# 02_-_POWER.net
KiCad netlist of a schematic drawn in Altium Designer
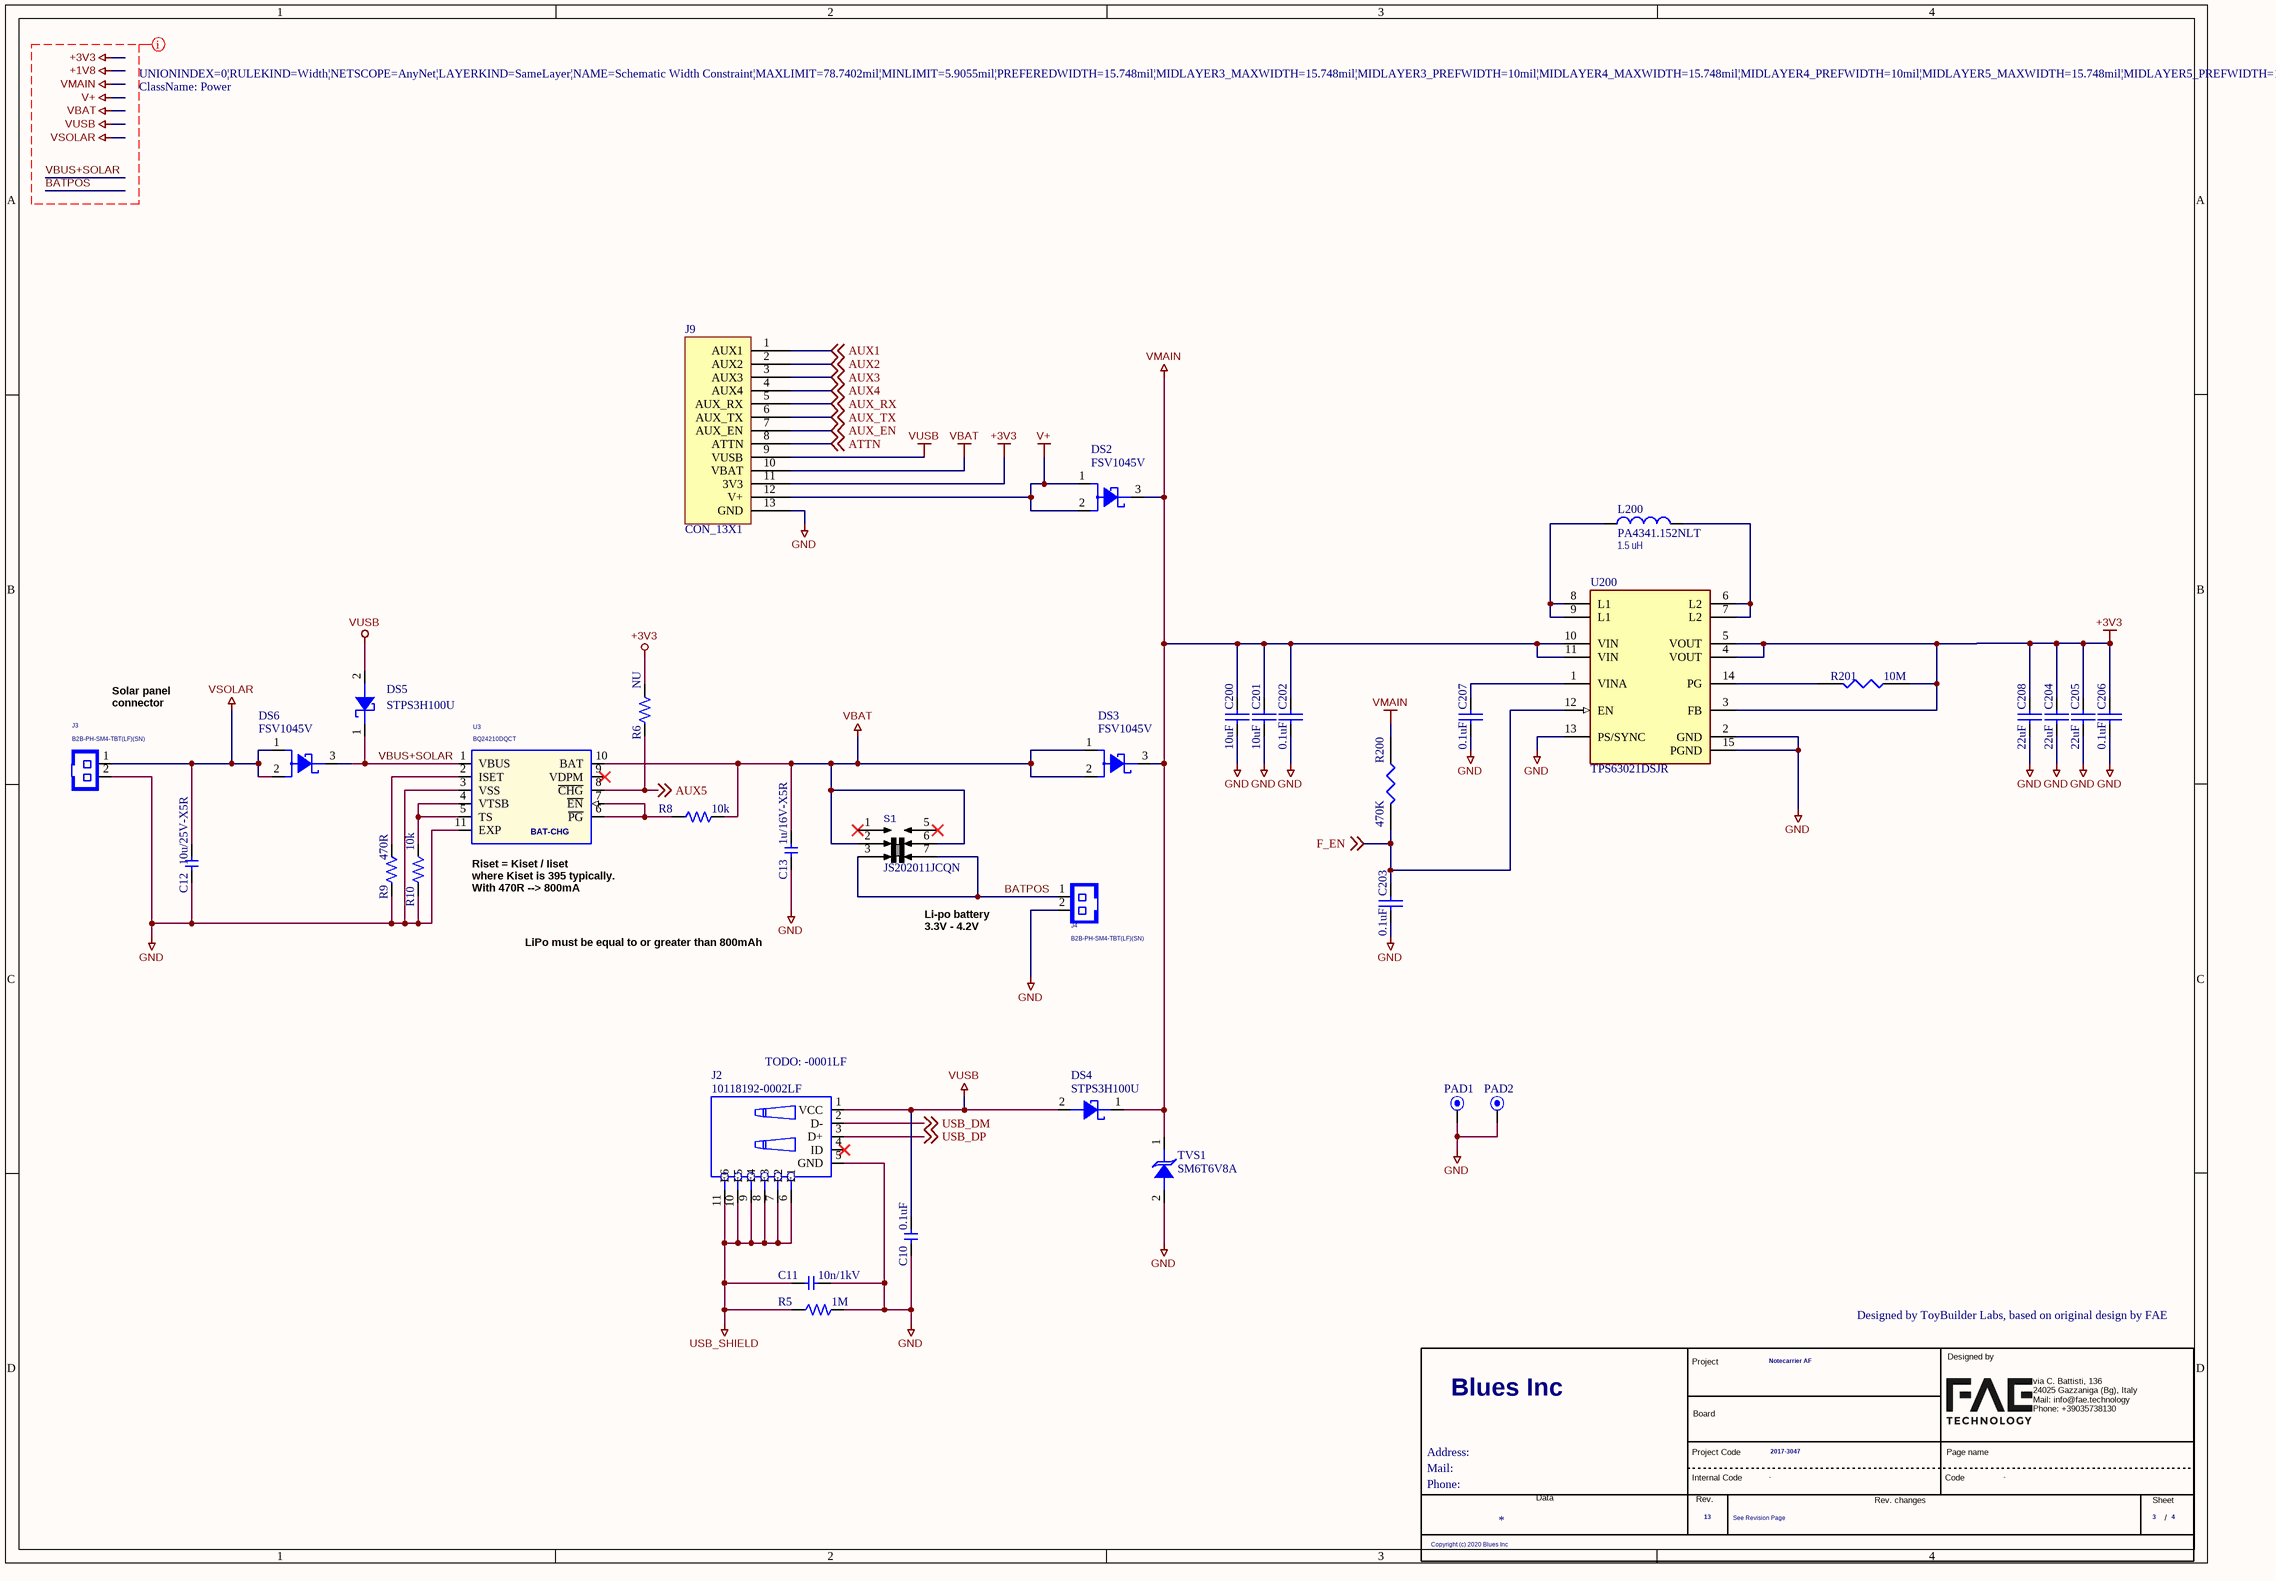
[diagram p0: 02 - POWER.SchDoc]

(export (version "E")
  (design (tool "Eeschema 10.0.6"))
  (components
    (comp (ref "*")
      (value "MyBlues")
      (fields
        (field (name "ADDRESS") "Address:")
        (field (name "COPYRIGHT") "Copyright (c) 2020 Blues Inc")
        (field (name "CUSTOMER CODE") "-")
        (field (name "CUSTOMERNAME") "Blues Inc")
        (field (name "DATABASE") "-")
        (field (name "DOCUMENTOREV") "See Revision Page")
        (field (name "MAIL") "Mail:")
        (field (name "NOME PROGETTO") "Notecarrier AF")
        (field (name "PAGE COUNT") "4")
        (field (name "PAGE NUMBER") "3")
        (field (name "PHONE") "Phone:")
        (field (name "PROJECT CODE") "2017-3047")
        (field (name "REVISION") "13")
      )
      (libsource (lib "*") (part "MyBlues"))
    )
    (comp (ref "C10")
      (value "0.1uF")
      (footprint "CS-C-0402")
      (description "CHIP CAP.CER. 100nF 16V 10% X7R 0402")
      (fields (field (name "MFR") "Yageo"))
      (libsource (lib "*") (part "CS-C-0402-100n/16V"))
    )
    (comp (ref "C11")
      (value "10n/1kV")
      (footprint "CS-C-1206")
      (description "CHIP CAP.CER. 10nF 1000V 10% X7R 1206")
      (libsource (lib "*") (part "CS-C-1206-10n/1kV"))
    )
    (comp (ref "C12")
      (value "10u/25V-X5R")
      (footprint "CS-C-1206")
      (description "CHIP CAP.CER. 10uF 25V X5R 10% 1206")
      (libsource (lib "*") (part "CS-C-1206-10u/25V-X5R"))
    )
    (comp (ref "C13")
      (value "1u/16V-X5R")
      (footprint "CS-C-0402")
      (description "CHIP CAP.CER. 1uF 16V 10% X5R 0402")
      (libsource (lib "*") (part "CS-C-0402-1u/16-X5R"))
    )
    (comp (ref "C200")
      (value "10uF")
      (footprint "0805_C")
      (description "CHIP CAP.CER. 10uF 16V 10% X7R 0805")
      (fields (field (name "MFR") "TDK"))
      (libsource (lib "Cap_SCH") (part "CAP"))
    )
    (comp (ref "C201")
      (value "10uF")
      (footprint "0805_C")
      (description "CHIP CAP.CER. 10uF 16V 10% X7R 0805")
      (fields (field (name "MFR") "TDK"))
      (libsource (lib "Cap_SCH") (part "CAP"))
    )
    (comp (ref "C202")
      (value "0.1uF")
      (footprint "CS-C-0402")
      (description "CHIP CAP.CER. 100nF 16V 10% X7R 0402")
      (fields (field (name "MFR") "Yageo"))
      (libsource (lib "Cap_SCH") (part "CAP"))
    )
    (comp (ref "C203")
      (value "0.1uF")
      (footprint "CS-C-0402")
      (description "CHIP CAP.CER. 100nF 16V 10% X7R 0402")
      (fields (field (name "MFR") "Yageo"))
      (libsource (lib "Cap_SCH") (part "CAP"))
    )
    (comp (ref "C204")
      (value "22uF")
      (footprint "0805_C")
      (description "CHIP CAP.CER. 22uF 16V 10% X7R 0805")
      (fields (field (name "MFR") "TDK"))
      (libsource (lib "Cap_SCH") (part "CAP"))
    )
    (comp (ref "C205")
      (value "22uF")
      (footprint "0805_C")
      (description "CHIP CAP.CER. 22uF 16V 10% X7R 0805")
      (fields (field (name "MFR") "TDK"))
      (libsource (lib "Cap_SCH") (part "CAP"))
    )
    (comp (ref "C206")
      (value "0.1uF")
      (footprint "CS-C-0402")
      (description "CHIP CAP.CER. 100nF 16V 10% X7R 0402")
      (fields (field (name "MFR") "Yageo"))
      (libsource (lib "Cap_SCH") (part "CAP"))
    )
    (comp (ref "C207")
      (value "0.1uF")
      (footprint "CS-C-0402")
      (description "CHIP CAP.CER. 100nF 16V 10% X7R 0402")
      (fields (field (name "MFR") "Yageo"))
      (libsource (lib "Cap_SCH") (part "CAP"))
    )
    (comp (ref "C208")
      (value "22uF")
      (footprint "0805_C")
      (description "CHIP CAP.CER. 22uF 16V 10% X7R 0805")
      (fields (field (name "MFR") "TDK"))
      (libsource (lib "Cap_SCH") (part "CAP"))
    )
    (comp (ref "DS2")
      (value "FSV1045V")
      (footprint "TO277-3")
      (description "DIODO SCHOTTKY 10A 45V FSV1045V TO277-3 SMT")
      (libsource (lib "*") (part "SCHOTTKY - FSV1045V - 10A/45V"))
    )
    (comp (ref "DS3")
      (value "FSV1045V")
      (footprint "TO277-3")
      (description "DIODO SCHOTTKY 10A 45V FSV1045V TO277-3 SMT")
      (libsource (lib "*") (part "SCHOTTKY - FSV1045V - 10A/45V"))
    )
    (comp (ref "DS4")
      (value "STPS3H100U")
      (footprint "SMB")
      (description "DIODO SCHOTTKY 3A 100V STPS3H100U SMB SMT")
      (libsource (lib "*") (part "SCHOTTKY-STPS3H100U - 3A/100V"))
    )
    (comp (ref "DS5")
      (value "STPS3H100U")
      (footprint "SMB")
      (description "DIODO SCHOTTKY 3A 100V STPS3H100U SMB SMT")
      (libsource (lib "*") (part "SCHOTTKY-STPS3H100U - 3A/100V"))
    )
    (comp (ref "DS6")
      (value "FSV1045V")
      (footprint "TO277-3")
      (description "DIODO SCHOTTKY 10A 45V FSV1045V TO277-3 SMT")
      (libsource (lib "*") (part "SCHOTTKY - FSV1045V - 10A/45V"))
    )
    (comp (ref "J2")
      (value "10118192-0002LF")
      (footprint "J-5-0065-FOS-MICROUSB10118192")
      (description "CONN. USB F/90° TIPO MICRO-B C.S. 10118192-0002LF FCI SMT")
      (libsource (lib "*") (part "USB - uUSB-B-10118192-0002LF"))
    )
    (comp (ref "J3")
      (value "B2B-PH-SM4-TBT(LF)(SN)")
      (footprint "J-2-0200-MDS-B2B-PH-SM4")
      (description "CONN. PH 2P M/D P=2 B2B-PH-SM4-TBT(LF)(SN) JST SMT")
      (libsource (lib "*") (part "PH - J-2-0200-MDS-B2B-PH-SM4"))
    )
    (comp (ref "J4")
      (value "B2B-PH-SM4-TBT(LF)(SN)")
      (footprint "J-2-0200-MDS-B2B-PH-SM4")
      (description "CONN. PH 2P M/D P=2 B2B-PH-SM4-TBT(LF)(SN) JST SMT")
      (libsource (lib "") (part "PH - J-2-0200-MDS-B2B-PH-SM4_1"))
    )
    (comp (ref "J9")
      (value "CON_13X1")
      (footprint "WE13S - 2.54")
      (libsource (lib "ATA_BLS_002_NTCR_A0-01_SCHLIB") (part "CON_13X1"))
    )
    (comp (ref "L200")
      (value "PA4341.152NLT")
      (footprint "PULSE PA4341.XXXNLT")
      (description "1.5uH, 9A SMD, (7.6 x 6.9 mm, 3.0 mm highi) 15 mOhm")
      (fields (field (name "MANUFACTURER") "Pulse") (field (name "INDUCTANCE") "1.5 uH"))
      (libsource (lib "TBL Inductors") (part "PA4341.152NLT"))
    )
    (comp (ref "PAD1")
      (value "TPS")
      (footprint "PAD-THT-CAS-0100")
      (description "Mounting Pads")
      (libsource (lib "*") (part "CASTELLATED PAD - 0100"))
    )
    (comp (ref "PAD2")
      (value "TPS")
      (footprint "PAD-THT-CAS-0100")
      (description "Mounting Pads")
      (libsource (lib "*") (part "CASTELLATED PAD - 0100"))
    )
    (comp (ref "R5")
      (value "1M")
      (footprint "RS-1206")
      (description "CHIP RES. 1M 1206 1/4W 1%")
      (libsource (lib "*") (part "RS-1206-1M"))
    )
    (comp (ref "R6")
      (value "NU")
      (footprint "RS-0402")
      (description "CHIP RES. 10K 0402 1/16W 1%")
      (libsource (lib "*") (part "RS-0402-10k"))
    )
    (comp (ref "R8")
      (value "10k")
      (footprint "RS-0402")
      (description "CHIP RES. 10K 0402 1/16W 1%")
      (libsource (lib "*") (part "RS-0402-10k"))
    )
    (comp (ref "R9")
      (value "470R")
      (footprint "RS-0402")
      (description "CHIP RES. 470R 0402 1/16W 1%")
      (libsource (lib "*") (part "RS-0402-470r"))
    )
    (comp (ref "R10")
      (value "10k")
      (footprint "RS-0402")
      (description "CHIP RES. 10K 0402 1/16W 1%")
      (libsource (lib "*") (part "RS-0402-10k"))
    )
    (comp (ref "R200")
      (value "470K")
      (footprint "RS-0402")
      (description "CHIP RES. 470K 0402 1/16W 1%")
      (fields (field (name "MFR") "Vishay / Dale"))
      (libsource (lib "Res_SCH") (part "R1_S"))
    )
    (comp (ref "R201")
      (value "10M")
      (footprint "RS-0402")
      (description "CHIP RES. 10M 0402 1/16W 1%")
      (fields (field (name "MFR") "Vishay / Dale"))
      (libsource (lib "Res_SCH") (part "R1_S"))
    )
    (comp (ref "S1")
      (value "JS202011JCQN")
      (footprint "CK_JS202011JCQN")
      (description "SWITCH SLIDE DPDT 300MA 6V, SMD, J-lead")
      (fields (field (name "MANUFACTURER") "ITT C&K"))
      (libsource (lib "TBL Switches and Buttons") (part "CK_JS202011JCQN"))
    )
    (comp (ref "TVS1")
      (value "SM6T6V8A")
      (footprint "SMB")
      (description "DIODO TVS TRANSIL UNIDIR. 600W 6.8V SM6T6V8A SMB SMT")
      (libsource (lib "*") (part "TVS-UNI - SM6T6V8A - 6.8V/600W"))
    )
    (comp (ref "U3")
      (value "BQ24210DQCT")
      (footprint "WSON10-EXP")
      (description "INTEGRATO BQ24210DQCT TEXAS WSON10 SMT")
      (libsource (lib "*") (part "BAT-CHARGE - BQ24210DQCT"))
    )
    (comp (ref "U200")
      (value "TPS63021DSJR")
      (footprint "FP-DSJ0014A-MFG")
      (description "IC REG BCK BST 3.3V 3.5A 14VSON")
      (fields
        (field (name "MANUFACTURER") "Texas Instruments")
        (field (name "OCTOPART") "https://octopart.com/tps63021dsjr-texas+instruments-17659431")
      )
      (libsource (lib "Altium Content Vault") (part "65dfafb52e5c3d3d60c9dfe8dd4b050"))
    )
  )
  (nets
    (net (code "2") (name "+3V3") (class "Default")
      (node (ref "C204") (pin "1") (pinfunction "1_1") (pintype "passive"))
      (node (ref "C205") (pin "1") (pinfunction "1_1") (pintype "passive"))
      (node (ref "C206") (pin "1") (pinfunction "1_1") (pintype "passive"))
      (node (ref "C208") (pin "1") (pinfunction "1_1") (pintype "passive"))
      (node (ref "J9") (pin "11") (pinfunction "3V3_11") (pintype "passive"))
      (node (ref "R201") (pin "1") (pinfunction "1_1") (pintype "passive"))
      (node (ref "R6") (pin "2") (pinfunction "2_2") (pintype "passive"))
      (node (ref "U200") (pin "3") (pinfunction "FB_3") (pintype "passive"))
      (node (ref "U200") (pin "4") (pinfunction "VOUT_4") (pintype "power_in"))
      (node (ref "U200") (pin "5") (pinfunction "VOUT_5") (pintype "power_in"))
    )
    (net (code "3") (name "/BATPOS") (class "Default")
      (node (ref "J4") (pin "1") (pinfunction "1_1") (pintype "passive"))
      (node (ref "S1") (pin "3") (pinfunction "3_3") (pintype "passive"))
      (node (ref "S1") (pin "7") (pinfunction "7_7") (pintype "passive"))
    )
    (net (code "4") (name "/VBUS+SOLAR") (class "Default")
      (node (ref "DS5") (pin "1") (pinfunction "C_1") (pintype "passive"))
      (node (ref "DS6") (pin "3") (pinfunction "C_3") (pintype "passive"))
      (node (ref "U3") (pin "1") (pinfunction "VBUS_1") (pintype "power_in"))
    )
    (net (code "5") (name "ATTN") (class "Default")
      (node (ref "J9") (pin "8") (pinfunction "ATTN_8") (pintype "passive"))
    )
    (net (code "6") (name "AUX1") (class "Default")
      (node (ref "J9") (pin "1") (pinfunction "AUX1_1") (pintype "passive"))
    )
    (net (code "7") (name "AUX2") (class "Default")
      (node (ref "J9") (pin "2") (pinfunction "AUX2_2") (pintype "passive"))
    )
    (net (code "8") (name "AUX3") (class "Default")
      (node (ref "J9") (pin "3") (pinfunction "AUX3_3") (pintype "passive"))
    )
    (net (code "9") (name "AUX4") (class "Default")
      (node (ref "J9") (pin "4") (pinfunction "AUX4_4") (pintype "passive"))
    )
    (net (code "10") (name "AUX5") (class "Default")
      (node (ref "R6") (pin "1") (pinfunction "1_1") (pintype "passive"))
      (node (ref "U3") (pin "8") (pinfunction "~{CHG}_8") (pintype "open_collector"))
    )
    (net (code "11") (name "AUX_EN") (class "Default")
      (node (ref "J9") (pin "7") (pinfunction "AUX_EN_7") (pintype "passive"))
    )
    (net (code "12") (name "AUX_RX") (class "Default")
      (node (ref "J9") (pin "5") (pinfunction "AUX_RX_5") (pintype "passive"))
    )
    (net (code "13") (name "AUX_TX") (class "Default")
      (node (ref "J9") (pin "6") (pinfunction "AUX_TX_6") (pintype "passive"))
    )
    (net (code "14") (name "F_EN") (class "Default")
      (node (ref "C203") (pin "1") (pinfunction "1_1") (pintype "passive"))
      (node (ref "R200") (pin "2") (pinfunction "2_2") (pintype "passive"))
      (node (ref "U200") (pin "12") (pinfunction "EN_12") (pintype "input"))
    )
    (net (code "15") (name "GND") (class "Default")
      (node (ref "C10") (pin "2") (pinfunction "2_2") (pintype "passive"))
      (node (ref "C11") (pin "2") (pinfunction "2_2") (pintype "passive"))
      (node (ref "C12") (pin "2") (pinfunction "2_2") (pintype "passive"))
      (node (ref "C13") (pin "2") (pinfunction "2_2") (pintype "passive"))
      (node (ref "C200") (pin "2") (pinfunction "2_2") (pintype "passive"))
      (node (ref "C201") (pin "2") (pinfunction "2_2") (pintype "passive"))
      (node (ref "C202") (pin "2") (pinfunction "2_2") (pintype "passive"))
      (node (ref "C203") (pin "2") (pinfunction "2_2") (pintype "passive"))
      (node (ref "C204") (pin "2") (pinfunction "2_2") (pintype "passive"))
      (node (ref "C205") (pin "2") (pinfunction "2_2") (pintype "passive"))
      (node (ref "C206") (pin "2") (pinfunction "2_2") (pintype "passive"))
      (node (ref "C207") (pin "2") (pinfunction "2_2") (pintype "passive"))
      (node (ref "C208") (pin "2") (pinfunction "2_2") (pintype "passive"))
      (node (ref "J2") (pin "5") (pinfunction "GND_5") (pintype "power_in"))
      (node (ref "J3") (pin "2") (pinfunction "2_2") (pintype "passive"))
      (node (ref "J4") (pin "2") (pinfunction "2_2") (pintype "passive"))
      (node (ref "J9") (pin "13") (pinfunction "GND_13") (pintype "passive"))
      (node (ref "PAD1") (pin "1") (pinfunction "1_1") (pintype "passive"))
      (node (ref "PAD2") (pin "1") (pinfunction "1_1") (pintype "passive"))
      (node (ref "R10") (pin "1") (pinfunction "1_1") (pintype "passive"))
      (node (ref "R5") (pin "2") (pinfunction "2_2") (pintype "passive"))
      (node (ref "R9") (pin "1") (pinfunction "1_1") (pintype "passive"))
      (node (ref "TVS1") (pin "2") (pinfunction "A_2") (pintype "passive"))
      (node (ref "U200") (pin "13") (pinfunction "PS/SYNC_13") (pintype "passive"))
      (node (ref "U200") (pin "15") (pinfunction "PGND_15") (pintype "power_in"))
      (node (ref "U200") (pin "2") (pinfunction "GND_2") (pintype "power_in"))
      (node (ref "U3") (pin "11") (pinfunction "EXP_11") (pintype "passive"))
      (node (ref "U3") (pin "3") (pinfunction "VSS_3") (pintype "power_in"))
    )
    (net (code "16") (name "Net-(L200-Pad1)") (class "Default")
      (node (ref "L200") (pin "1") (pinfunction "1_1") (pintype "passive"))
      (node (ref "U200") (pin "8") (pinfunction "L1_8") (pintype "passive"))
      (node (ref "U200") (pin "9") (pinfunction "L1_9") (pintype "passive"))
    )
    (net (code "17") (name "Net-(L200-Pad2)") (class "Default")
      (node (ref "L200") (pin "2") (pinfunction "2_2") (pintype "passive"))
      (node (ref "U200") (pin "6") (pinfunction "L2_6") (pintype "passive"))
      (node (ref "U200") (pin "7") (pinfunction "L2_7") (pintype "passive"))
    )
    (net (code "18") (name "Net-(U3-ISET)") (class "Default")
      (node (ref "R9") (pin "2") (pinfunction "2_2") (pintype "passive"))
      (node (ref "U3") (pin "2") (pinfunction "ISET_2") (pintype "passive"))
    )
    (net (code "19") (name "Net-(U3-TS)") (class "Default")
      (node (ref "R10") (pin "2") (pinfunction "2_2") (pintype "passive"))
      (node (ref "U3") (pin "4") (pinfunction "VTSB_4") (pintype "passive"))
      (node (ref "U3") (pin "5") (pinfunction "TS_5") (pintype "passive"))
    )
    (net (code "20") (name "Net-(U3-~{EN})") (class "Default")
      (node (ref "R8") (pin "1") (pinfunction "1_1") (pintype "passive"))
      (node (ref "U3") (pin "6") (pinfunction "~{PG}_6") (pintype "open_collector"))
      (node (ref "U3") (pin "7") (pinfunction "~{EN}_7") (pintype "input"))
    )
    (net (code "21") (name "Net-(U200-PG)") (class "Default")
      (node (ref "R201") (pin "2") (pinfunction "2_2") (pintype "passive"))
      (node (ref "U200") (pin "14") (pinfunction "PG_14") (pintype "open_collector"))
    )
    (net (code "22") (name "Net-(U200-VINA)") (class "Default")
      (node (ref "C207") (pin "1") (pinfunction "1_1") (pintype "passive"))
      (node (ref "U200") (pin "1") (pinfunction "VINA_1") (pintype "power_in"))
    )
    (net (code "23") (name "USB_DM") (class "Default")
      (node (ref "J2") (pin "2") (pinfunction "D-_2") (pintype "bidirectional"))
    )
    (net (code "24") (name "USB_DP") (class "Default")
      (node (ref "J2") (pin "3") (pinfunction "D+_3") (pintype "bidirectional"))
    )
    (net (code "25") (name "USB_SHIELD") (class "Default")
      (node (ref "C11") (pin "1") (pinfunction "1_1") (pintype "passive"))
      (node (ref "J2") (pin "10") (pinfunction "E5_10") (pintype "passive"))
      (node (ref "J2") (pin "11") (pinfunction "E6_11") (pintype "passive"))
      (node (ref "J2") (pin "6") (pinfunction "E1_6") (pintype "passive"))
      (node (ref "J2") (pin "7") (pinfunction "E2_7") (pintype "passive"))
      (node (ref "J2") (pin "8") (pinfunction "E3_8") (pintype "passive"))
      (node (ref "J2") (pin "9") (pinfunction "E4_9") (pintype "passive"))
      (node (ref "R5") (pin "1") (pinfunction "1_1") (pintype "passive"))
    )
    (net (code "26") (name "V+") (class "Default")
      (node (ref "DS2") (pin "1") (pinfunction "A1_1") (pintype "passive"))
      (node (ref "DS2") (pin "2") (pinfunction "A2_2") (pintype "passive"))
      (node (ref "J9") (pin "12") (pinfunction "V+_12") (pintype "passive"))
    )
    (net (code "27") (name "VBAT") (class "Default")
      (node (ref "C13") (pin "1") (pinfunction "1_1") (pintype "passive"))
      (node (ref "DS3") (pin "1") (pinfunction "A1_1") (pintype "passive"))
      (node (ref "DS3") (pin "2") (pinfunction "A2_2") (pintype "passive"))
      (node (ref "J9") (pin "10") (pinfunction "VBAT_10") (pintype "passive"))
      (node (ref "R8") (pin "2") (pinfunction "2_2") (pintype "passive"))
      (node (ref "S1") (pin "2") (pinfunction "2_2") (pintype "passive"))
      (node (ref "S1") (pin "6") (pinfunction "6_6") (pintype "passive"))
      (node (ref "U3") (pin "10") (pinfunction "BAT_10") (pintype "power_in"))
    )
    (net (code "28") (name "VMAIN") (class "Default")
      (node (ref "C200") (pin "1") (pinfunction "1_1") (pintype "passive"))
      (node (ref "C201") (pin "1") (pinfunction "1_1") (pintype "passive"))
      (node (ref "C202") (pin "1") (pinfunction "1_1") (pintype "passive"))
      (node (ref "DS2") (pin "3") (pinfunction "C_3") (pintype "passive"))
      (node (ref "DS3") (pin "3") (pinfunction "C_3") (pintype "passive"))
      (node (ref "DS4") (pin "1") (pinfunction "C_1") (pintype "passive"))
      (node (ref "R200") (pin "1") (pinfunction "1_1") (pintype "passive"))
      (node (ref "TVS1") (pin "1") (pinfunction "C_1") (pintype "passive"))
      (node (ref "U200") (pin "10") (pinfunction "VIN_10") (pintype "power_in"))
      (node (ref "U200") (pin "11") (pinfunction "VIN_11") (pintype "power_in"))
    )
    (net (code "29") (name "VSOLAR") (class "Default")
      (node (ref "C12") (pin "1") (pinfunction "1_1") (pintype "passive"))
      (node (ref "DS6") (pin "1") (pinfunction "A1_1") (pintype "passive"))
      (node (ref "DS6") (pin "2") (pinfunction "A2_2") (pintype "passive"))
      (node (ref "J3") (pin "1") (pinfunction "1_1") (pintype "passive"))
    )
    (net (code "30") (name "VUSB") (class "Default")
      (node (ref "C10") (pin "1") (pinfunction "1_1") (pintype "passive"))
      (node (ref "DS4") (pin "2") (pinfunction "A_2") (pintype "passive"))
      (node (ref "DS5") (pin "2") (pinfunction "A_2") (pintype "passive"))
      (node (ref "J2") (pin "1") (pinfunction "VCC_1") (pintype "power_in"))
      (node (ref "J9") (pin "9") (pinfunction "VUSB_9") (pintype "passive"))
    )
    (net (code "31") (name "unconnected-(J2-ID-Pad4)") (class "Default")
      (node (ref "J2") (pin "4") (pinfunction "ID_4") (pintype "passive+no_connect"))
    )
    (net (code "32") (name "unconnected-(S1-Pad1)") (class "Default")
      (node (ref "S1") (pin "1") (pinfunction "1_1") (pintype "passive+no_connect"))
    )
    (net (code "33") (name "unconnected-(S1-Pad5)") (class "Default")
      (node (ref "S1") (pin "5") (pinfunction "5_5") (pintype "passive+no_connect"))
    )
    (net (code "34") (name "unconnected-(U3-VDPM-Pad9)") (class "Default")
      (node (ref "U3") (pin "9") (pinfunction "VDPM_9") (pintype "passive+no_connect"))
    )
  )
)
